# breakoutsch.net
KiCad netlist of a schematic drawn in EAGLE
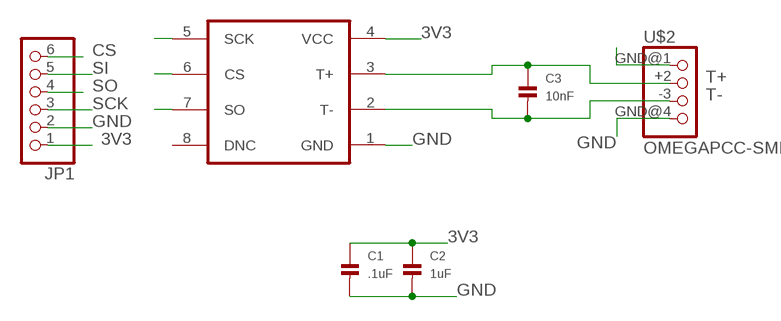
[diagram p0: schematic, sheet 1]

(export (version "E")
  (design (tool "Eeschema 10.0.6"))
  (components
    (comp (ref "C1")
      (value ".1uF")
      (footprint "eagle-import:0603")
      (libsource (lib "eagle-import") (part "CAP_CERAMIC0603"))
    )
    (comp (ref "C2")
      (value "1uF")
      (footprint "eagle-import:0603")
      (libsource (lib "eagle-import") (part "CAP_CERAMIC0603"))
    )
    (comp (ref "C3")
      (value "10nF")
      (footprint "eagle-import:0603")
      (libsource (lib "eagle-import") (part "CAP_CERAMIC0603"))
    )
    (comp (ref "JP1")
      (value "HEADER-1X6ROUND")
      (footprint "eagle-import:1X06_ROUND")
      (libsource (lib "eagle-import") (part "HEADER-1X6ROUND"))
    )
    (comp (ref "U$1")
      (value "MAX31855")
      (footprint "eagle-import:SO-08")
      (libsource (lib "eagle-import") (part "MAX31855"))
    )
    (comp (ref "U$2")
      (value "OMEGAPCC-SMP")
      (footprint "eagle-import:PCC-SMP")
      (libsource (lib "eagle-import") (part "OMEGAPCC-SMP"))
    )
  )
  (nets
    (net (code "1") (name "/3V3") (class "Default")
      (node (ref "C1") (pin "1") (pinfunction "P$1_1") (pintype "passive"))
      (node (ref "C2") (pin "1") (pinfunction "P$1_1") (pintype "passive"))
      (node (ref "JP1") (pin "1") (pinfunction "1_1") (pintype "passive"))
      (node (ref "U$1") (pin "4") (pinfunction "VCC_4") (pintype "bidirectional"))
    )
    (net (code "2") (name "/CS") (class "Default")
      (node (ref "JP1") (pin "6") (pinfunction "6_6") (pintype "passive"))
      (node (ref "U$1") (pin "6") (pinfunction "CS_6") (pintype "bidirectional"))
    )
    (net (code "3") (name "/GND") (class "Default")
      (node (ref "C1") (pin "2") (pinfunction "P$2_2") (pintype "passive"))
      (node (ref "C2") (pin "2") (pinfunction "P$2_2") (pintype "passive"))
      (node (ref "JP1") (pin "2") (pinfunction "2_2") (pintype "passive"))
      (node (ref "U$1") (pin "1") (pinfunction "GND_1") (pintype "bidirectional"))
      (node (ref "U$2") (pin "GND@1") (pinfunction "1_GND@1") (pintype "passive"))
      (node (ref "U$2") (pin "GND@4") (pinfunction "4_GND@4") (pintype "passive"))
    )
    (net (code "4") (name "/SCK") (class "Default")
      (node (ref "JP1") (pin "3") (pinfunction "3_3") (pintype "passive"))
      (node (ref "U$1") (pin "5") (pinfunction "SCK_5") (pintype "bidirectional"))
    )
    (net (code "5") (name "/SI") (class "Default")
      (node (ref "JP1") (pin "5") (pinfunction "5_5") (pintype "passive"))
    )
    (net (code "6") (name "/SO") (class "Default")
      (node (ref "JP1") (pin "4") (pinfunction "4_4") (pintype "passive"))
      (node (ref "U$1") (pin "7") (pinfunction "SO_7") (pintype "bidirectional"))
    )
    (net (code "7") (name "/T+") (class "Default")
      (node (ref "C3") (pin "1") (pinfunction "P$1_1") (pintype "passive"))
      (node (ref "U$1") (pin "3") (pinfunction "T+_3") (pintype "bidirectional"))
      (node (ref "U$2") (pin "+2") (pinfunction "2_+2") (pintype "passive"))
    )
    (net (code "8") (name "/T-") (class "Default")
      (node (ref "C3") (pin "2") (pinfunction "P$2_2") (pintype "passive"))
      (node (ref "U$1") (pin "2") (pinfunction "T-_2") (pintype "bidirectional"))
      (node (ref "U$2") (pin "-3") (pinfunction "3_-3") (pintype "passive"))
    )
    (net (code "9") (name "unconnected-(U$1-DNC-Pad8)") (class "Default")
      (node (ref "U$1") (pin "8") (pinfunction "DNC_8") (pintype "bidirectional"))
    )
  )
)
